# rpi-lirc.net
KiCad netlist of a schematic drawn in EAGLE
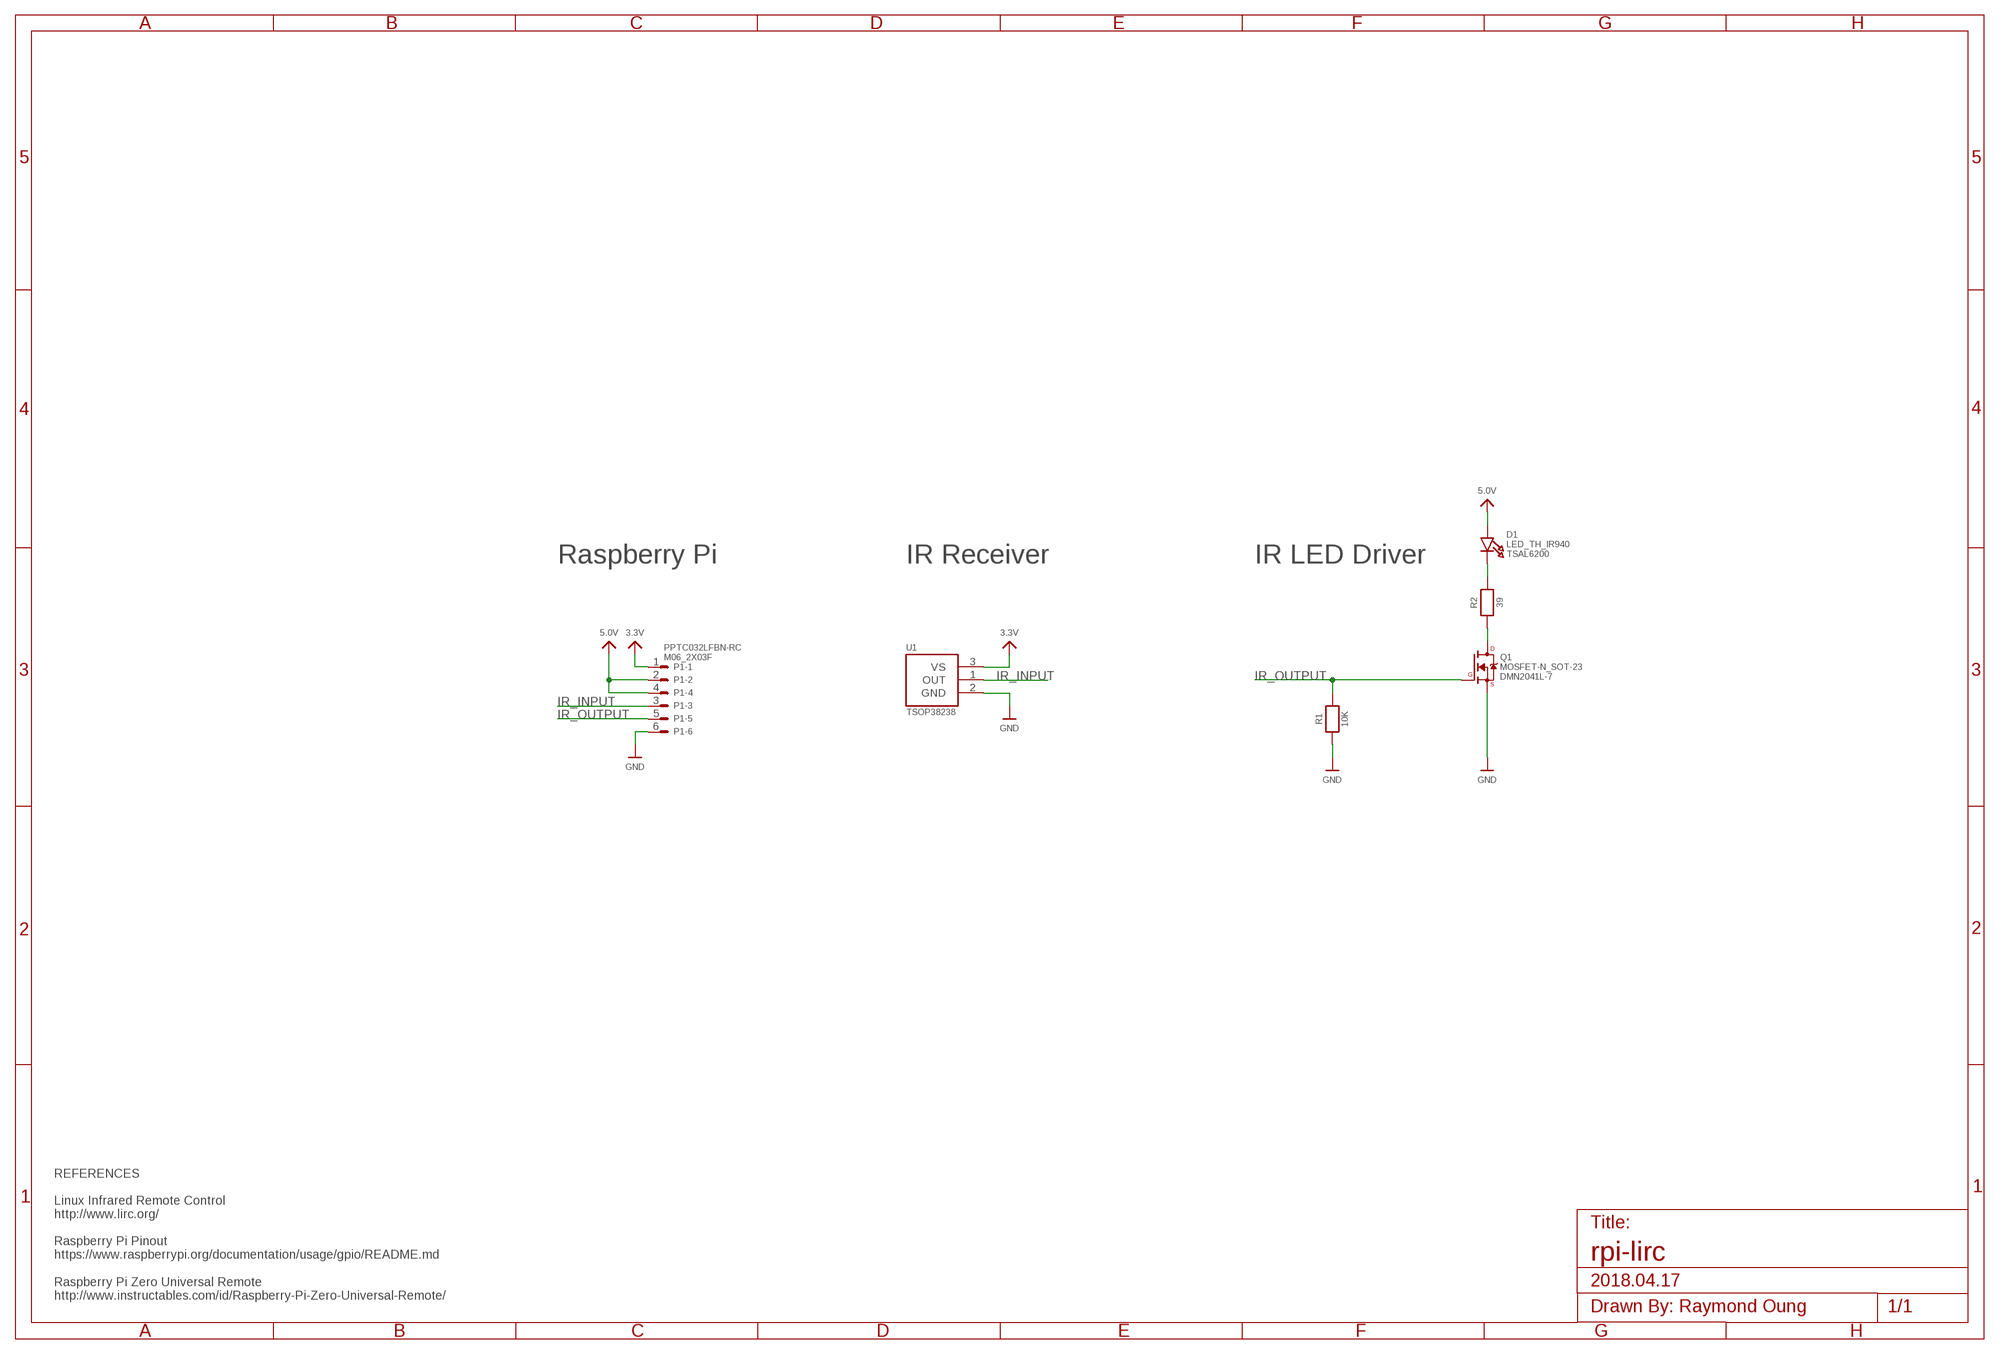
[diagram p0: schematic, sheet 1]

(export (version "E")
  (design (tool "Eeschema 10.0.6"))
  (components
    (comp (ref "D1")
      (value "LED_TH_IR940")
      (footprint "eagle-import:RADIAL_5MM")
      (fields (field (name "PARTID") "TSAL6200"))
      (libsource (lib "eagle-import") (part "LED_TH_IR940"))
    )
    (comp (ref "P1")
      (value "M06_2X03F")
      (footprint "eagle-import:2X03_LOCK")
      (fields (field (name "PARTID") "PPTC032LFBN-RC"))
      (libsource (lib "eagle-import") (part "M06_2X03F"))
    )
    (comp (ref "Q1")
      (value "MOSFET-N_SOT-23")
      (footprint "eagle-import:SOT23-3")
      (fields (field (name "PARTID") "DMN2041L-7"))
      (libsource (lib "eagle-import") (part "MOSFET-N_SOT-23"))
    )
    (comp (ref "R1")
      (value "10K")
      (footprint "eagle-import:0603")
      (libsource (lib "eagle-import") (part "RESISTOR_0603_10K"))
    )
    (comp (ref "R2")
      (value "39")
      (footprint "eagle-import:0603")
      (libsource (lib "eagle-import") (part "RESISTOR_0603"))
    )
    (comp (ref "U1")
      (value "TSOP38238")
      (footprint "eagle-import:TSOP38238")
      (libsource (lib "eagle-import") (part "TSOP38238"))
    )
  )
  (nets
    (net (code "1") (name "/IR_INPUT") (class "Default")
      (node (ref "P1") (pin "3") (pinfunction "S_3") (pintype "passive"))
      (node (ref "U1") (pin "1") (pinfunction "OUT_1") (pintype "output"))
    )
    (net (code "2") (name "/IR_OUTPUT") (class "Default")
      (node (ref "P1") (pin "5") (pinfunction "S_5") (pintype "passive"))
      (node (ref "Q1") (pin "1") (pinfunction "G_1") (pintype "bidirectional"))
      (node (ref "R1") (pin "2") (pinfunction "2_2") (pintype "passive"))
    )
    (net (code "3") (name "3.3V") (class "Default")
      (node (ref "P1") (pin "1") (pinfunction "S_1") (pintype "passive"))
      (node (ref "U1") (pin "3") (pinfunction "VS_3") (pintype "power_in"))
    )
    (net (code "4") (name "5.0V") (class "Default")
      (node (ref "D1") (pin "A") (pinfunction "A_A") (pintype "passive"))
      (node (ref "P1") (pin "2") (pinfunction "S_2") (pintype "passive"))
      (node (ref "P1") (pin "4") (pinfunction "S_4") (pintype "passive"))
    )
    (net (code "5") (name "GND") (class "Default")
      (node (ref "P1") (pin "6") (pinfunction "S_6") (pintype "passive"))
      (node (ref "Q1") (pin "2") (pinfunction "S_2") (pintype "bidirectional"))
      (node (ref "R1") (pin "1") (pinfunction "1_1") (pintype "passive"))
      (node (ref "U1") (pin "2") (pinfunction "GND_2") (pintype "power_in"))
    )
    (net (code "6") (name "Net-(D1-PadC)") (class "Default")
      (node (ref "D1") (pin "C") (pinfunction "C_C") (pintype "passive"))
      (node (ref "R2") (pin "2") (pinfunction "2_2") (pintype "passive"))
    )
    (net (code "7") (name "Net-(Q1-D)") (class "Default")
      (node (ref "Q1") (pin "3") (pinfunction "D_3") (pintype "bidirectional"))
      (node (ref "R2") (pin "1") (pinfunction "1_1") (pintype "passive"))
    )
  )
)
